# RK3399_Display_HDMI_EDP.net
KiCad netlist of a schematic drawn in Altium Designer
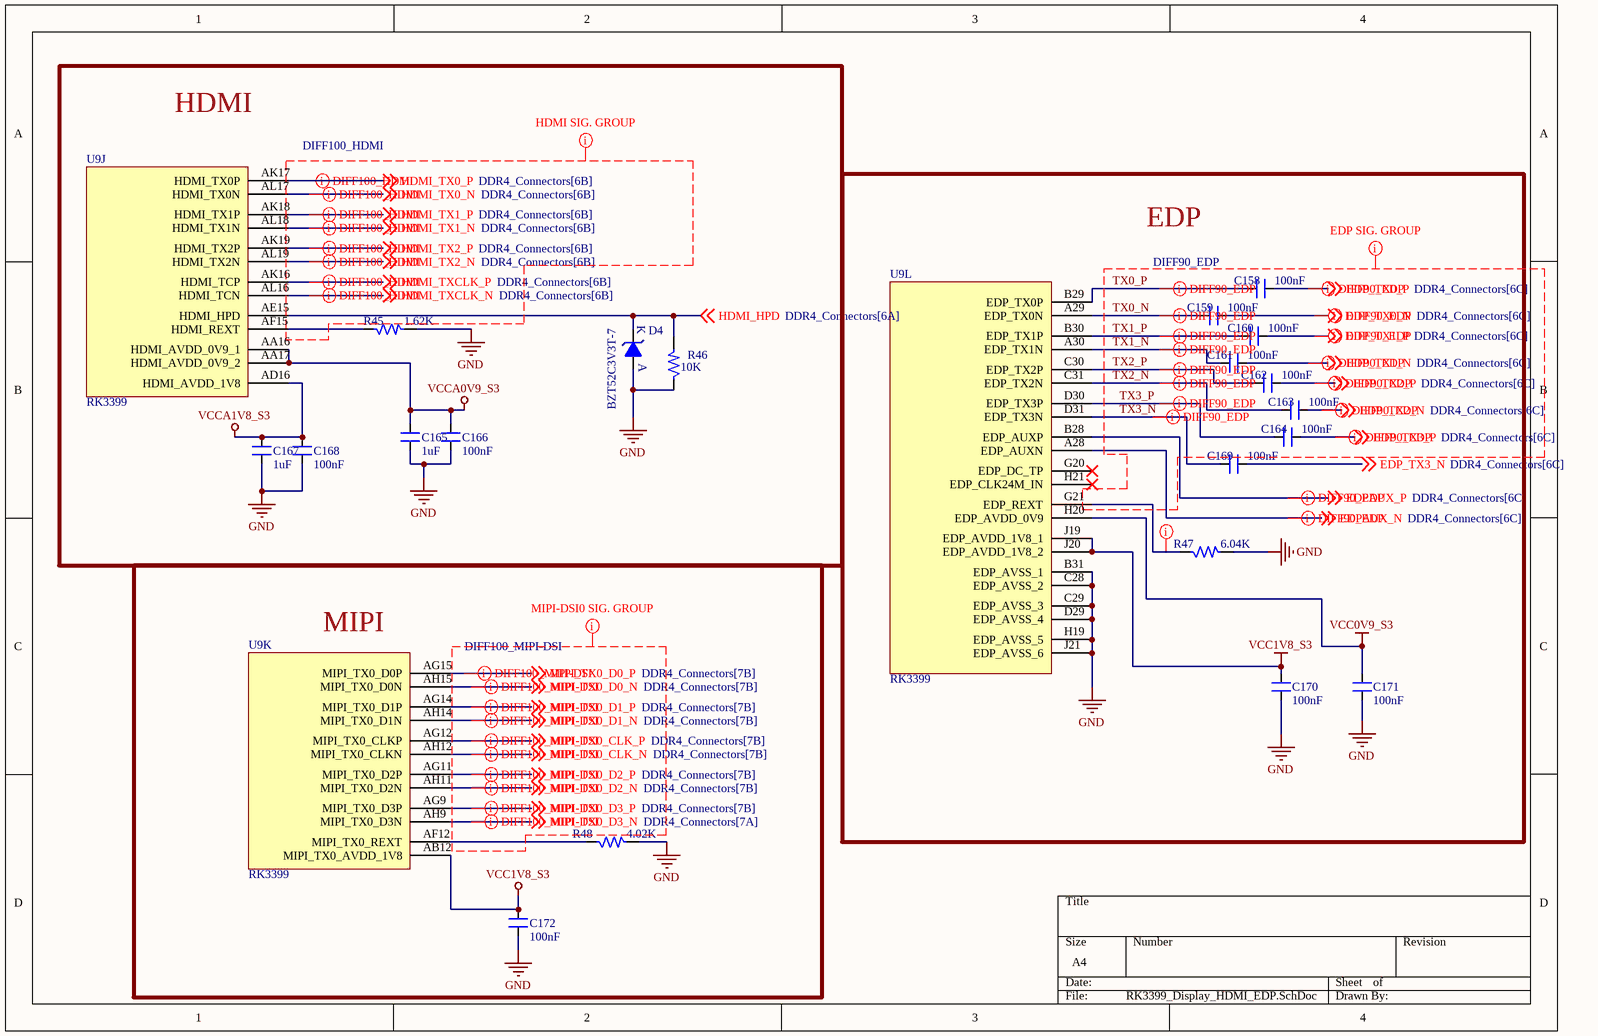
[diagram p0: RK3399_Display_HDMI_EDP.SchDoc]

(export (version "E")
  (design (tool "Eeschema 10.0.6"))
  (components
    (comp (ref "C158")
      (value "100nF")
      (footprint "CAP_0201")
      (description "0.1µF ±10% 25V Ceramic Capacitor X5R 0201 (0603 Metric)")
      (fields
        (field (name "MANUFACTURER") "TDK Corporation")
        (field (name "MANUFACTURER PART NUMBER") "C0603X5R1E104K030BB")
      )
      (libsource (lib "EsteemPCB_SOM_Course_schlib") (part "CAP_100nF-25V-10%-0201"))
    )
    (comp (ref "C159")
      (value "100nF")
      (footprint "CAP_0201")
      (description "0.1µF ±10% 25V Ceramic Capacitor X5R 0201 (0603 Metric)")
      (fields
        (field (name "MANUFACTURER") "TDK Corporation")
        (field (name "MANUFACTURER PART NUMBER") "C0603X5R1E104K030BB")
      )
      (libsource (lib "EsteemPCB_SOM_Course_schlib") (part "CAP_100nF-25V-10%-0201"))
    )
    (comp (ref "C160")
      (value "100nF")
      (footprint "CAP_0201")
      (description "0.1µF ±10% 25V Ceramic Capacitor X5R 0201 (0603 Metric)")
      (fields
        (field (name "MANUFACTURER") "TDK Corporation")
        (field (name "MANUFACTURER PART NUMBER") "C0603X5R1E104K030BB")
      )
      (libsource (lib "EsteemPCB_SOM_Course_schlib") (part "CAP_100nF-25V-10%-0201"))
    )
    (comp (ref "C161")
      (value "100nF")
      (footprint "CAP_0201")
      (description "0.1µF ±10% 25V Ceramic Capacitor X5R 0201 (0603 Metric)")
      (fields
        (field (name "MANUFACTURER") "TDK Corporation")
        (field (name "MANUFACTURER PART NUMBER") "C0603X5R1E104K030BB")
      )
      (libsource (lib "EsteemPCB_SOM_Course_schlib") (part "CAP_100nF-25V-10%-0201"))
    )
    (comp (ref "C162")
      (value "100nF")
      (footprint "CAP_0201")
      (description "0.1µF ±10% 25V Ceramic Capacitor X5R 0201 (0603 Metric)")
      (fields
        (field (name "MANUFACTURER") "TDK Corporation")
        (field (name "MANUFACTURER PART NUMBER") "C0603X5R1E104K030BB")
      )
      (libsource (lib "EsteemPCB_SOM_Course_schlib") (part "CAP_100nF-25V-10%-0201"))
    )
    (comp (ref "C163")
      (value "100nF")
      (footprint "CAP_0201")
      (description "0.1µF ±10% 25V Ceramic Capacitor X5R 0201 (0603 Metric)")
      (fields
        (field (name "MANUFACTURER") "TDK Corporation")
        (field (name "MANUFACTURER PART NUMBER") "C0603X5R1E104K030BB")
      )
      (libsource (lib "EsteemPCB_SOM_Course_schlib") (part "CAP_100nF-25V-10%-0201"))
    )
    (comp (ref "C164")
      (value "100nF")
      (footprint "CAP_0201")
      (description "0.1µF ±10% 25V Ceramic Capacitor X5R 0201 (0603 Metric)")
      (fields
        (field (name "MANUFACTURER") "TDK Corporation")
        (field (name "MANUFACTURER PART NUMBER") "C0603X5R1E104K030BB")
      )
      (libsource (lib "EsteemPCB_SOM_Course_schlib") (part "CAP_100nF-25V-10%-0201"))
    )
    (comp (ref "C165")
      (value "1uF")
      (footprint "CAP_0201")
      (description "1µF ±20% 16V Ceramic Capacitor X5R 0201 (0603 Metric)")
      (fields
        (field (name "MANUFACTURER") "Samsung Electro-Mechanics")
        (field (name "MANUFACTURER PART NUMBER") "CL03A105MO3NRNH")
      )
      (libsource (lib "EsteemPCB_SOM_Course_schlib") (part "CAP_1uF-16V-10%-0201"))
    )
    (comp (ref "C166")
      (value "100nF")
      (footprint "CAP_0201")
      (description "0.1µF ±10% 25V Ceramic Capacitor X5R 0201 (0603 Metric)")
      (fields
        (field (name "MANUFACTURER") "TDK Corporation")
        (field (name "MANUFACTURER PART NUMBER") "C0603X5R1E104K030BB")
      )
      (libsource (lib "EsteemPCB_SOM_Course_schlib") (part "CAP_100nF-25V-10%-0201"))
    )
    (comp (ref "C167")
      (value "1uF")
      (footprint "CAP_0201")
      (description "1µF ±20% 16V Ceramic Capacitor X5R 0201 (0603 Metric)")
      (fields
        (field (name "MANUFACTURER") "Samsung Electro-Mechanics")
        (field (name "MANUFACTURER PART NUMBER") "CL03A105MO3NRNH")
      )
      (libsource (lib "EsteemPCB_SOM_Course_schlib") (part "CAP_1uF-16V-10%-0201"))
    )
    (comp (ref "C168")
      (value "100nF")
      (footprint "CAP_0201")
      (description "0.1µF ±10% 25V Ceramic Capacitor X5R 0201 (0603 Metric)")
      (fields
        (field (name "MANUFACTURER") "TDK Corporation")
        (field (name "MANUFACTURER PART NUMBER") "C0603X5R1E104K030BB")
      )
      (libsource (lib "EsteemPCB_SOM_Course_schlib") (part "CAP_100nF-25V-10%-0201"))
    )
    (comp (ref "C169")
      (value "100nF")
      (footprint "CAP_0201")
      (description "0.1µF ±10% 25V Ceramic Capacitor X5R 0201 (0603 Metric)")
      (fields
        (field (name "MANUFACTURER") "TDK Corporation")
        (field (name "MANUFACTURER PART NUMBER") "C0603X5R1E104K030BB")
      )
      (libsource (lib "EsteemPCB_SOM_Course_schlib") (part "CAP_100nF-25V-10%-0201"))
    )
    (comp (ref "C170")
      (value "100nF")
      (footprint "CAP_0201")
      (description "0.1µF ±10% 25V Ceramic Capacitor X5R 0201 (0603 Metric)")
      (fields
        (field (name "MANUFACTURER") "TDK Corporation")
        (field (name "MANUFACTURER PART NUMBER") "C0603X5R1E104K030BB")
      )
      (libsource (lib "EsteemPCB_SOM_Course_schlib") (part "CAP_100nF-25V-10%-0201"))
    )
    (comp (ref "C171")
      (value "100nF")
      (footprint "CAP_0201")
      (description "0.1µF ±10% 25V Ceramic Capacitor X5R 0201 (0603 Metric)")
      (fields
        (field (name "MANUFACTURER") "TDK Corporation")
        (field (name "MANUFACTURER PART NUMBER") "C0603X5R1E104K030BB")
      )
      (libsource (lib "EsteemPCB_SOM_Course_schlib") (part "CAP_100nF-25V-10%-0201"))
    )
    (comp (ref "C172")
      (value "100nF")
      (footprint "CAP_0201")
      (description "0.1µF ±10% 25V Ceramic Capacitor X5R 0201 (0603 Metric)")
      (fields
        (field (name "MANUFACTURER") "TDK Corporation")
        (field (name "MANUFACTURER PART NUMBER") "C0603X5R1E104K030BB")
      )
      (libsource (lib "EsteemPCB_SOM_Course_schlib") (part "CAP_100nF-25V-10%-0201"))
    )
    (comp (ref "D4")
      (value "BZT52C3V3T-7")
      (footprint "DIO_SOD523")
      (description "Zener Diode 3.3V 300mW ±6% Surface Mount SOD-523")
      (fields (field (name "MANUFACTURER") "Diodes Incorporated"))
      (libsource (lib "EsteemPCB_SOM_Course_schlib") (part "DIO-Z_3.3V-300mW-SOD-523"))
    )
    (comp (ref "R45")
      (value "1.62K")
      (footprint "RES_0201")
      (description "1.62 kOhms ±1% 0.05W, 1/20W Chip Resistor 0201 (0603 Metric) Automotive AEC-Q200 Thick Film")
      (fields
        (field (name "MANUFACTURER") "Panasonic Electronic Components")
        (field (name "MANUFACTURER PART NUMBER") "ERJ-1GNF1621C")
      )
      (libsource (lib "EsteemPCB_SOM_Course_schlib") (part "RES_1.62K-0.05W-1%-0201"))
    )
    (comp (ref "R46")
      (value "10K")
      (footprint "RES_0201")
      (description "10 kOhms ±1% 0.05W, 1/20W Chip Resistor 0201 (0603 Metric) Thick Film")
      (fields
        (field (name "MANUFACTURER") "Stackpole Electronics Inc")
        (field (name "MANUFACTURER PART NUMBER") "RMCF0201FT10K0")
      )
      (libsource (lib "EsteemPCB_SOM_Course_schlib") (part "RES_10K-0.05W-1%-0201"))
    )
    (comp (ref "R47")
      (value "6.04K")
      (footprint "RES_0201")
      (description "6.04 kOhms ±1% 0.05W, 1/20W Chip Resistor 0201 (0603 Metric) Thick Film")
      (fields
        (field (name "MANUFACTURER") "Panasonic Electronic Components")
        (field (name "MANUFACTURER PART NUMBER") "ERJ-1GEF6041C")
      )
      (libsource (lib "EsteemPCB_SOM_Course_schlib") (part "RES_6.04K-0.05W-1%-0201"))
    )
    (comp (ref "R48")
      (value "4.02K")
      (footprint "RES_0201")
      (description "4.02 kOhms ±1% 0.05W, 1/20W Chip Resistor 0201 (0603 Metric) Thick Film")
      (fields
        (field (name "MANUFACTURER") "Yageo")
        (field (name "MANUFACTURER PART NUMBER") "RC0201FR-074K02L")
      )
      (libsource (lib "EsteemPCB_SOM_Course_schlib") (part "RES_4.02K-0.05W-1%-0201"))
    )
    (comp (ref "U9")
      (value "RK3399")
      (footprint "FBGA828_23_826X826")
      (description "RK3399 is a low power, high performance processor for computing, personal mobile.")
      (fields (field (name "MANUFACTURER") "Rockchip"))
      (libsource (lib "EsteemPCB_SOM_Course_schlib") (part "IC_RK3399-FCBGA828"))
    )
  )
  (nets
    (net (code "1") (name "/TX0_N") (class "Default")
      (node (ref "C159") (pin "2") (pinfunction "2_2") (pintype "passive"))
      (node (ref "U9") (pin "A29") (pinfunction "EDP_TX0N_A29") (pintype "passive"))
    )
    (net (code "2") (name "/TX0_P") (class "Default")
      (node (ref "C158") (pin "2") (pinfunction "2_2") (pintype "passive"))
      (node (ref "U9") (pin "B29") (pinfunction "EDP_TX0P_B29") (pintype "passive"))
    )
    (net (code "3") (name "/TX1_N") (class "Default")
      (node (ref "C161") (pin "2") (pinfunction "2_2") (pintype "passive"))
      (node (ref "U9") (pin "A30") (pinfunction "EDP_TX1N_A30") (pintype "passive"))
    )
    (net (code "4") (name "/TX1_P") (class "Default")
      (node (ref "C160") (pin "2") (pinfunction "2_2") (pintype "passive"))
      (node (ref "U9") (pin "B30") (pinfunction "EDP_TX1P_B30") (pintype "passive"))
    )
    (net (code "5") (name "/TX2_N") (class "Default")
      (node (ref "C163") (pin "2") (pinfunction "2_2") (pintype "passive"))
      (node (ref "U9") (pin "C31") (pinfunction "EDP_TX2N_C31") (pintype "passive"))
    )
    (net (code "6") (name "/TX2_P") (class "Default")
      (node (ref "C162") (pin "2") (pinfunction "2_2") (pintype "passive"))
      (node (ref "U9") (pin "C30") (pinfunction "EDP_TX2P_C30") (pintype "passive"))
    )
    (net (code "7") (name "/TX3_N") (class "Default")
      (node (ref "C169") (pin "2") (pinfunction "2_2") (pintype "passive"))
      (node (ref "U9") (pin "D31") (pinfunction "EDP_TX3N_D31") (pintype "passive"))
    )
    (net (code "8") (name "/TX3_P") (class "Default")
      (node (ref "C164") (pin "2") (pinfunction "2_2") (pintype "passive"))
      (node (ref "U9") (pin "D30") (pinfunction "EDP_TX3P_D30") (pintype "passive"))
    )
    (net (code "9") (name "EDPAUX_N") (class "Default")
      (node (ref "U9") (pin "A28") (pinfunction "EDP_AUXN_A28") (pintype "passive"))
    )
    (net (code "10") (name "EDPAUX_P") (class "Default")
      (node (ref "U9") (pin "B28") (pinfunction "EDP_AUXP_B28") (pintype "passive"))
    )
    (net (code "11") (name "EDP_TX0_N") (class "Default")
      (node (ref "C159") (pin "1") (pinfunction "1_1") (pintype "passive"))
    )
    (net (code "12") (name "EDP_TX0_P") (class "Default")
      (node (ref "C158") (pin "1") (pinfunction "1_1") (pintype "passive"))
    )
    (net (code "13") (name "EDP_TX1_N") (class "Default")
      (node (ref "C161") (pin "1") (pinfunction "1_1") (pintype "passive"))
    )
    (net (code "14") (name "EDP_TX1_P") (class "Default")
      (node (ref "C160") (pin "1") (pinfunction "1_1") (pintype "passive"))
    )
    (net (code "15") (name "EDP_TX2_N") (class "Default")
      (node (ref "C163") (pin "1") (pinfunction "1_1") (pintype "passive"))
    )
    (net (code "16") (name "EDP_TX2_P") (class "Default")
      (node (ref "C162") (pin "1") (pinfunction "1_1") (pintype "passive"))
    )
    (net (code "17") (name "EDP_TX3_N") (class "Default")
      (node (ref "C169") (pin "1") (pinfunction "1_1") (pintype "passive"))
    )
    (net (code "18") (name "EDP_TX3_P") (class "Default")
      (node (ref "C164") (pin "1") (pinfunction "1_1") (pintype "passive"))
    )
    (net (code "19") (name "GND") (class "Default")
      (node (ref "C165") (pin "1") (pinfunction "1_1") (pintype "passive"))
      (node (ref "C166") (pin "1") (pinfunction "1_1") (pintype "passive"))
      (node (ref "C167") (pin "1") (pinfunction "1_1") (pintype "passive"))
      (node (ref "C168") (pin "1") (pinfunction "1_1") (pintype "passive"))
      (node (ref "C170") (pin "2") (pinfunction "2_2") (pintype "passive"))
      (node (ref "C171") (pin "2") (pinfunction "2_2") (pintype "passive"))
      (node (ref "C172") (pin "1") (pinfunction "1_1") (pintype "passive"))
      (node (ref "D4") (pin "A") (pinfunction "A_A") (pintype "passive"))
      (node (ref "R45") (pin "2") (pinfunction "2_2") (pintype "passive"))
      (node (ref "R46") (pin "1") (pinfunction "1_1") (pintype "passive"))
      (node (ref "R47") (pin "2") (pinfunction "2_2") (pintype "passive"))
      (node (ref "R48") (pin "2") (pinfunction "2_2") (pintype "passive"))
      (node (ref "U9") (pin "B31") (pinfunction "EDP_AVSS_1_B31") (pintype "passive"))
      (node (ref "U9") (pin "C28") (pinfunction "EDP_AVSS_2_C28") (pintype "passive"))
      (node (ref "U9") (pin "C29") (pinfunction "EDP_AVSS_3_C29") (pintype "passive"))
      (node (ref "U9") (pin "D29") (pinfunction "EDP_AVSS_4_D29") (pintype "passive"))
      (node (ref "U9") (pin "H19") (pinfunction "EDP_AVSS_5_H19") (pintype "passive"))
      (node (ref "U9") (pin "J21") (pinfunction "EDP_AVSS_6_J21") (pintype "passive"))
    )
    (net (code "20") (name "HDMI_HPD") (class "Default")
      (node (ref "D4") (pin "K") (pinfunction "K_K") (pintype "passive"))
      (node (ref "R46") (pin "2") (pinfunction "2_2") (pintype "passive"))
      (node (ref "U9") (pin "AE15") (pinfunction "HDMI_HPD_AE15") (pintype "passive"))
    )
    (net (code "21") (name "HDMI_TX0_N") (class "Default")
      (node (ref "U9") (pin "AL17") (pinfunction "HDMI_TX0N_AL17") (pintype "passive"))
    )
    (net (code "22") (name "HDMI_TX0_P") (class "Default")
      (node (ref "U9") (pin "AK17") (pinfunction "HDMI_TX0P_AK17") (pintype "passive"))
    )
    (net (code "23") (name "HDMI_TX1_N") (class "Default")
      (node (ref "U9") (pin "AL18") (pinfunction "HDMI_TX1N_AL18") (pintype "passive"))
    )
    (net (code "24") (name "HDMI_TX1_P") (class "Default")
      (node (ref "U9") (pin "AK18") (pinfunction "HDMI_TX1P_AK18") (pintype "passive"))
    )
    (net (code "25") (name "HDMI_TX2_N") (class "Default")
      (node (ref "U9") (pin "AL19") (pinfunction "HDMI_TX2N_AL19") (pintype "passive"))
    )
    (net (code "26") (name "HDMI_TX2_P") (class "Default")
      (node (ref "U9") (pin "AK19") (pinfunction "HDMI_TX2P_AK19") (pintype "passive"))
    )
    (net (code "27") (name "HDMI_TXCLK_N") (class "Default")
      (node (ref "U9") (pin "AL16") (pinfunction "HDMI_TCN_AL16") (pintype "passive"))
    )
    (net (code "28") (name "HDMI_TXCLK_P") (class "Default")
      (node (ref "U9") (pin "AK16") (pinfunction "HDMI_TCP_AK16") (pintype "passive"))
    )
    (net (code "29") (name "MIPI_TX0_CLK_N") (class "Default")
      (node (ref "U9") (pin "AH12") (pinfunction "MIPI_TX0_CLKN_AH12") (pintype "passive"))
    )
    (net (code "30") (name "MIPI_TX0_CLK_P") (class "Default")
      (node (ref "U9") (pin "AG12") (pinfunction "MIPI_TX0_CLKP_AG12") (pintype "passive"))
    )
    (net (code "31") (name "MIPI_TX0_D0_N") (class "Default")
      (node (ref "U9") (pin "AH15") (pinfunction "MIPI_TX0_D0N_AH15") (pintype "passive"))
    )
    (net (code "32") (name "MIPI_TX0_D0_P") (class "Default")
      (node (ref "U9") (pin "AG15") (pinfunction "MIPI_TX0_D0P_AG15") (pintype "passive"))
    )
    (net (code "33") (name "MIPI_TX0_D1_N") (class "Default")
      (node (ref "U9") (pin "AH14") (pinfunction "MIPI_TX0_D1N_AH14") (pintype "passive"))
    )
    (net (code "34") (name "MIPI_TX0_D1_P") (class "Default")
      (node (ref "U9") (pin "AG14") (pinfunction "MIPI_TX0_D1P_AG14") (pintype "passive"))
    )
    (net (code "35") (name "MIPI_TX0_D2_N") (class "Default")
      (node (ref "U9") (pin "AH11") (pinfunction "MIPI_TX0_D2N_AH11") (pintype "passive"))
    )
    (net (code "36") (name "MIPI_TX0_D2_P") (class "Default")
      (node (ref "U9") (pin "AG11") (pinfunction "MIPI_TX0_D2P_AG11") (pintype "passive"))
    )
    (net (code "37") (name "MIPI_TX0_D3_N") (class "Default")
      (node (ref "U9") (pin "AH9") (pinfunction "MIPI_TX0_D3N_AH9") (pintype "passive"))
    )
    (net (code "38") (name "MIPI_TX0_D3_P") (class "Default")
      (node (ref "U9") (pin "AG9") (pinfunction "MIPI_TX0_D3P_AG9") (pintype "passive"))
    )
    (net (code "39") (name "Net-(U9J-HDMI_REXT)") (class "Default")
      (node (ref "R45") (pin "1") (pinfunction "1_1") (pintype "passive"))
      (node (ref "U9") (pin "AF15") (pinfunction "HDMI_REXT_AF15") (pintype "passive"))
    )
    (net (code "40") (name "Net-(U9K-MIPI_TX0_REXT)") (class "Default")
      (node (ref "R48") (pin "1") (pinfunction "1_1") (pintype "passive"))
      (node (ref "U9") (pin "AF12") (pinfunction "MIPI_TX0_REXT_AF12") (pintype "passive"))
    )
    (net (code "41") (name "Net-(U9L-EDP_REXT)") (class "Default")
      (node (ref "R47") (pin "1") (pinfunction "1_1") (pintype "passive"))
      (node (ref "U9") (pin "G21") (pinfunction "EDP_REXT_G21") (pintype "passive"))
    )
    (net (code "42") (name "VCC0V9_S3") (class "Default")
      (node (ref "C171") (pin "1") (pinfunction "1_1") (pintype "passive"))
      (node (ref "U9") (pin "H20") (pinfunction "EDP_AVDD_0V9_H20") (pintype "passive"))
    )
    (net (code "43") (name "VCC1V8_S3") (class "Default")
      (node (ref "C170") (pin "1") (pinfunction "1_1") (pintype "passive"))
      (node (ref "C172") (pin "2") (pinfunction "2_2") (pintype "passive"))
      (node (ref "U9") (pin "AB12") (pinfunction "MIPI_TX0_AVDD_1V8_AB12") (pintype "passive"))
      (node (ref "U9") (pin "J19") (pinfunction "EDP_AVDD_1V8_1_J19") (pintype "passive"))
      (node (ref "U9") (pin "J20") (pinfunction "EDP_AVDD_1V8_2_J20") (pintype "passive"))
    )
    (net (code "44") (name "VCCA0V9_S3") (class "Default")
      (node (ref "C165") (pin "2") (pinfunction "2_2") (pintype "passive"))
      (node (ref "C166") (pin "2") (pinfunction "2_2") (pintype "passive"))
      (node (ref "U9") (pin "AA16") (pinfunction "HDMI_AVDD_0V9_1_AA16") (pintype "passive"))
      (node (ref "U9") (pin "AA17") (pinfunction "HDMI_AVDD_0V9_2_AA17") (pintype "passive"))
    )
    (net (code "45") (name "VCCA1V8_S3") (class "Default")
      (node (ref "C167") (pin "2") (pinfunction "2_2") (pintype "passive"))
      (node (ref "C168") (pin "2") (pinfunction "2_2") (pintype "passive"))
      (node (ref "U9") (pin "AD16") (pinfunction "HDMI_AVDD_1V8_AD16") (pintype "passive"))
    )
    (net (code "46") (name "unconnected-(U9L-EDP_CLK24M_IN-PadH21)") (class "Default")
      (node (ref "U9") (pin "H21") (pinfunction "EDP_CLK24M_IN_H21") (pintype "passive+no_connect"))
    )
    (net (code "47") (name "unconnected-(U9L-EDP_DC_TP-PadG20)") (class "Default")
      (node (ref "U9") (pin "G20") (pinfunction "EDP_DC_TP_G20") (pintype "passive+no_connect"))
    )
  )
)
